# tractor_2v2.net
KiCad netlist of a schematic drawn in EAGLE
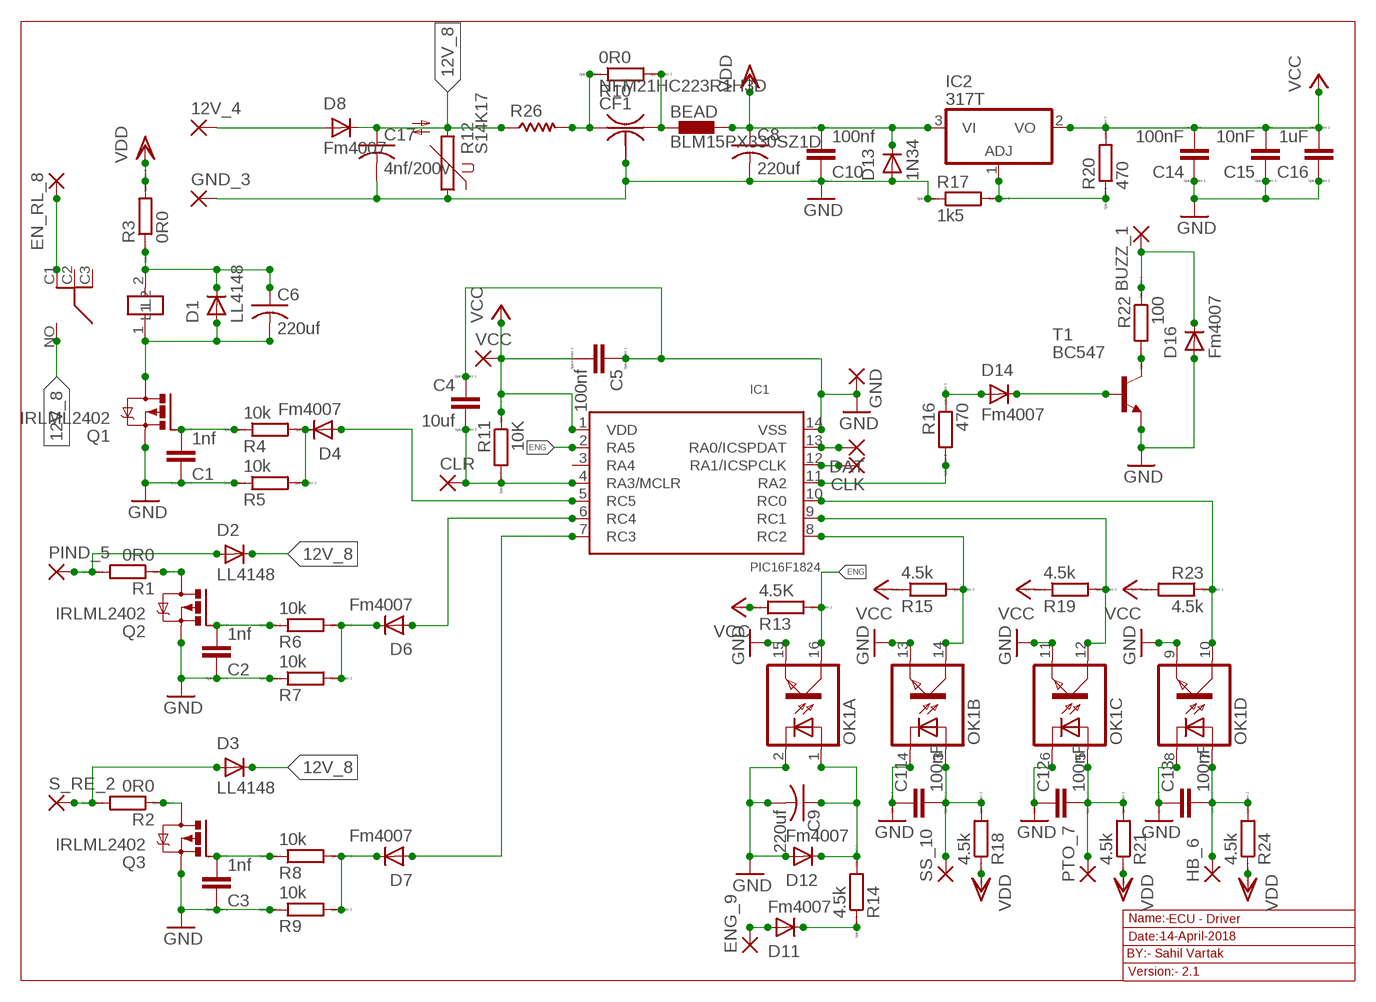
[diagram p0: schematic, sheet 1]

(export (version "E")
  (design (tool "Eeschema 10.0.6"))
  (components
    (comp (ref "12V_4")
      (value "2,54/1,1")
      (footprint "eagle-import:2,54_1,1")
      (libsource (lib "eagle-import") (part "2,54/1,1"))
    )
    (comp (ref "BEAD")
      (value "BLM15PX330SZ1D")
      (footprint "eagle-import:0402")
      (libsource (lib "eagle-import") (part "BLM15HG601SN1"))
    )
    (comp (ref "BUZZ_1")
      (value "2,54/1,1")
      (footprint "eagle-import:2,54_1,1")
      (libsource (lib "eagle-import") (part "2,54/1,1"))
    )
    (comp (ref "C1")
      (value "1nf")
      (footprint "eagle-import:C0603")
      (libsource (lib "eagle-import") (part "CC0603"))
    )
    (comp (ref "C2")
      (value "1nf")
      (footprint "eagle-import:C0603")
      (libsource (lib "eagle-import") (part "CC0603"))
    )
    (comp (ref "C3")
      (value "1nf")
      (footprint "eagle-import:C0603")
      (libsource (lib "eagle-import") (part "CC0603"))
    )
    (comp (ref "C4")
      (value "10uf")
      (footprint "eagle-import:C0603")
      (libsource (lib "eagle-import") (part "CC0603"))
    )
    (comp (ref "C5")
      (value "100nf")
      (footprint "eagle-import:C0603")
      (libsource (lib "eagle-import") (part "CC0603"))
    )
    (comp (ref "C6")
      (value "220uf")
      (footprint "eagle-import:C025-025X050")
      (libsource (lib "eagle-import") (part "C-US025-025X050"))
    )
    (comp (ref "C8")
      (value "220uf")
      (footprint "eagle-import:C025-025X050")
      (libsource (lib "eagle-import") (part "C-US025-025X050"))
    )
    (comp (ref "C9")
      (value "220uf")
      (footprint "eagle-import:C025-025X050")
      (libsource (lib "eagle-import") (part "C-US025-025X050"))
    )
    (comp (ref "C10")
      (value "100nf")
      (footprint "eagle-import:C0603")
      (libsource (lib "eagle-import") (part "CC0603"))
    )
    (comp (ref "C11")
      (value "100nF")
      (footprint "eagle-import:C0603")
      (libsource (lib "eagle-import") (part "CC0603"))
    )
    (comp (ref "C12")
      (value "100nF")
      (footprint "eagle-import:C0603")
      (libsource (lib "eagle-import") (part "CC0603"))
    )
    (comp (ref "C13")
      (value "100nF")
      (footprint "eagle-import:C0603")
      (libsource (lib "eagle-import") (part "CC0603"))
    )
    (comp (ref "C14")
      (value "100nF")
      (footprint "eagle-import:C0603")
      (libsource (lib "eagle-import") (part "CC0603"))
    )
    (comp (ref "C15")
      (value "10nF")
      (footprint "eagle-import:C0603")
      (libsource (lib "eagle-import") (part "CC0603"))
    )
    (comp (ref "C16")
      (value "1uF")
      (footprint "eagle-import:C0603")
      (libsource (lib "eagle-import") (part "CC0603"))
    )
    (comp (ref "C17")
      (value "4nf/200v")
      (footprint "eagle-import:C050-045X075")
      (libsource (lib "eagle-import") (part "C-US050-045X075"))
    )
    (comp (ref "CF1")
      (value "NFM21HC223R1H3D")
      (footprint "eagle-import:NFM3DC")
      (fields (field (name "MF") "FARNELL") (field (name "MPN") "NFM3DCC470U1H3L"))
      (libsource (lib "eagle-import") (part "NFM3DC"))
    )
    (comp (ref "CLK")
      (value "1,6/0,8")
      (footprint "eagle-import:1,6_0,8")
      (libsource (lib "eagle-import") (part "1,6/0,8"))
    )
    (comp (ref "CLR")
      (value "1,6/0,8")
      (footprint "eagle-import:1,6_0,8")
      (libsource (lib "eagle-import") (part "1,6/0,8"))
    )
    (comp (ref "D1")
      (value "LL4148")
      (footprint "eagle-import:SMA-DO214AC")
      (libsource (lib "eagle-import") (part "GF1"))
    )
    (comp (ref "D2")
      (value "LL4148")
      (footprint "eagle-import:SMA-DO214AC")
      (libsource (lib "eagle-import") (part "GF1"))
    )
    (comp (ref "D3")
      (value "LL4148")
      (footprint "eagle-import:SMA-DO214AC")
      (libsource (lib "eagle-import") (part "GF1"))
    )
    (comp (ref "D4")
      (value "Fm4007")
      (footprint "eagle-import:SMA-DO214AC")
      (libsource (lib "eagle-import") (part "GF1"))
    )
    (comp (ref "D6")
      (value "Fm4007")
      (footprint "eagle-import:SMA-DO214AC")
      (libsource (lib "eagle-import") (part "GF1"))
    )
    (comp (ref "D7")
      (value "Fm4007")
      (footprint "eagle-import:SMA-DO214AC")
      (libsource (lib "eagle-import") (part "GF1"))
    )
    (comp (ref "D8")
      (value "Fm4007")
      (footprint "eagle-import:SMA-DO214AC")
      (libsource (lib "eagle-import") (part "GF1"))
    )
    (comp (ref "D11")
      (value "Fm4007")
      (footprint "eagle-import:SMA-DO214AC")
      (libsource (lib "eagle-import") (part "GF1"))
    )
    (comp (ref "D12")
      (value "Fm4007")
      (footprint "eagle-import:SMA-DO214AC")
      (libsource (lib "eagle-import") (part "GF1"))
    )
    (comp (ref "D13")
      (value "1N34")
      (footprint "eagle-import:SMA-DO214AC")
      (libsource (lib "eagle-import") (part "GF1"))
    )
    (comp (ref "D14")
      (value "Fm4007")
      (footprint "eagle-import:SMA-DO214AC")
      (libsource (lib "eagle-import") (part "GF1"))
    )
    (comp (ref "D16")
      (value "Fm4007")
      (footprint "eagle-import:SMA-DO214AC")
      (libsource (lib "eagle-import") (part "GF1"))
    )
    (comp (ref "DAT")
      (value "1,6/0,8")
      (footprint "eagle-import:1,6_0,8")
      (libsource (lib "eagle-import") (part "1,6/0,8"))
    )
    (comp (ref "ENG_9")
      (value "2,54/1,1")
      (footprint "eagle-import:2,54_1,1")
      (libsource (lib "eagle-import") (part "2,54/1,1"))
    )
    (comp (ref "EN_RL_8")
      (value "2,54/1,1")
      (footprint "eagle-import:2,54_1,1")
      (libsource (lib "eagle-import") (part "2,54/1,1"))
    )
    (comp (ref "GND")
      (value "1,6/0,8")
      (footprint "eagle-import:1,6_0,8")
      (libsource (lib "eagle-import") (part "1,6/0,8"))
    )
    (comp (ref "GND_3")
      (value "2,54/1,1")
      (footprint "eagle-import:2,54_1,1")
      (libsource (lib "eagle-import") (part "2,54/1,1"))
    )
    (comp (ref "HB_6")
      (value "2,54/1,1")
      (footprint "eagle-import:2,54_1,1")
      (libsource (lib "eagle-import") (part "2,54/1,1"))
    )
    (comp (ref "IC1")
      (value "PIC16F1824")
      (footprint "eagle-import:SO-14")
      (libsource (lib "eagle-import") (part "PIC16F1824"))
    )
    (comp (ref "IC2")
      (value "317T")
      (footprint "eagle-import:TO220H")
      (libsource (lib "eagle-import") (part "317T"))
    )
    (comp (ref "K1")
      (value "RL703")
      (footprint "eagle-import:RL703")
      (libsource (lib "eagle-import") (part "RL703"))
    )
    (comp (ref "OK1")
      (value "TLP283-4")
      (footprint "eagle-import:MINI-FLAT-16")
      (libsource (lib "eagle-import") (part "TLP283-4"))
    )
    (comp (ref "PIND_5")
      (value "2,54/1,1")
      (footprint "eagle-import:2,54_1,1")
      (libsource (lib "eagle-import") (part "2,54/1,1"))
    )
    (comp (ref "PTO_7")
      (value "2,54/1,1")
      (footprint "eagle-import:2,54_1,1")
      (libsource (lib "eagle-import") (part "2,54/1,1"))
    )
    (comp (ref "Q1")
      (value "IRLML2402")
      (footprint "eagle-import:MICRO3")
      (libsource (lib "eagle-import") (part "IRLML5203"))
    )
    (comp (ref "Q2")
      (value "IRLML2402")
      (footprint "eagle-import:MICRO3")
      (libsource (lib "eagle-import") (part "IRLML5203"))
    )
    (comp (ref "Q3")
      (value "IRLML2402")
      (footprint "eagle-import:MICRO3")
      (libsource (lib "eagle-import") (part "IRLML5203"))
    )
    (comp (ref "R1")
      (value "0R0")
      (footprint "eagle-import:R0603")
      (libsource (lib "eagle-import") (part "RR0603"))
    )
    (comp (ref "R2")
      (value "0R0")
      (footprint "eagle-import:R0603")
      (libsource (lib "eagle-import") (part "RR0603"))
    )
    (comp (ref "R3")
      (value "0R0")
      (footprint "eagle-import:R0603")
      (libsource (lib "eagle-import") (part "RR0603"))
    )
    (comp (ref "R4")
      (value "10k")
      (footprint "eagle-import:R0603")
      (libsource (lib "eagle-import") (part "RR0603"))
    )
    (comp (ref "R5")
      (value "10k")
      (footprint "eagle-import:R0603")
      (libsource (lib "eagle-import") (part "RR0603"))
    )
    (comp (ref "R6")
      (value "10k")
      (footprint "eagle-import:R0603")
      (libsource (lib "eagle-import") (part "RR0603"))
    )
    (comp (ref "R7")
      (value "10k")
      (footprint "eagle-import:R0603")
      (libsource (lib "eagle-import") (part "RR0603"))
    )
    (comp (ref "R8")
      (value "10k")
      (footprint "eagle-import:R0603")
      (libsource (lib "eagle-import") (part "RR0603"))
    )
    (comp (ref "R9")
      (value "10k")
      (footprint "eagle-import:R0603")
      (libsource (lib "eagle-import") (part "RR0603"))
    )
    (comp (ref "R10")
      (value "0R0")
      (footprint "eagle-import:R0603")
      (libsource (lib "eagle-import") (part "RR0603"))
    )
    (comp (ref "R11")
      (value "10K")
      (footprint "eagle-import:R0603")
      (libsource (lib "eagle-import") (part "RR0603"))
    )
    (comp (ref "R12")
      (value "S14K17")
      (footprint "eagle-import:S14K17")
      (libsource (lib "eagle-import") (part "S14K17"))
    )
    (comp (ref "R13")
      (value "4.5K")
      (footprint "eagle-import:R0603")
      (libsource (lib "eagle-import") (part "RR0603"))
    )
    (comp (ref "R14")
      (value "4.5k")
      (footprint "eagle-import:R0603")
      (libsource (lib "eagle-import") (part "RR0603"))
    )
    (comp (ref "R15")
      (value "4.5k")
      (footprint "eagle-import:R0603")
      (libsource (lib "eagle-import") (part "RR0603"))
    )
    (comp (ref "R16")
      (value "470")
      (footprint "eagle-import:R0603")
      (libsource (lib "eagle-import") (part "RR0603"))
    )
    (comp (ref "R17")
      (value "1k5")
      (footprint "eagle-import:R0603")
      (libsource (lib "eagle-import") (part "RR0603"))
    )
    (comp (ref "R18")
      (value "4.5k")
      (footprint "eagle-import:R0603")
      (libsource (lib "eagle-import") (part "RR0603"))
    )
    (comp (ref "R19")
      (value "4.5k")
      (footprint "eagle-import:R0603")
      (libsource (lib "eagle-import") (part "RR0603"))
    )
    (comp (ref "R20")
      (value "470")
      (footprint "eagle-import:R0603")
      (libsource (lib "eagle-import") (part "RR0603"))
    )
    (comp (ref "R21")
      (value "4.5k")
      (footprint "eagle-import:R0603")
      (libsource (lib "eagle-import") (part "RR0603"))
    )
    (comp (ref "R22")
      (value "100")
      (footprint "eagle-import:R0603")
      (libsource (lib "eagle-import") (part "RR0603"))
    )
    (comp (ref "R23")
      (value "4.5k")
      (footprint "eagle-import:R0603")
      (libsource (lib "eagle-import") (part "RR0603"))
    )
    (comp (ref "R24")
      (value "4.5k")
      (footprint "eagle-import:R0603")
      (libsource (lib "eagle-import") (part "RR0603"))
    )
    (comp (ref "R26")
      (value "R-US_WSC2515")
      (footprint "eagle-import:WSC2515")
      (libsource (lib "eagle-import") (part "R-US_WSC2515"))
    )
    (comp (ref "SS_10")
      (value "2,54/1,1")
      (footprint "eagle-import:2,54_1,1")
      (libsource (lib "eagle-import") (part "2,54/1,1"))
    )
    (comp (ref "S_RE_2")
      (value "2,54/1,1")
      (footprint "eagle-import:2,54_1,1")
      (libsource (lib "eagle-import") (part "2,54/1,1"))
    )
    (comp (ref "T1")
      (value "BC547")
      (footprint "eagle-import:TO92")
      (libsource (lib "eagle-import") (part "BC547"))
    )
    (comp (ref "VCC")
      (value "1,6/0,8")
      (footprint "eagle-import:1,6_0,8")
      (libsource (lib "eagle-import") (part "1,6/0,8"))
    )
  )
  (nets
    (net (code "1") (name "12V_8") (class "Default")
      (node (ref "C17") (pin "1") (pinfunction "1_1") (pintype "passive"))
      (node (ref "D2") (pin "K") (pinfunction "C_K") (pintype "passive"))
      (node (ref "D3") (pin "K") (pinfunction "C_K") (pintype "passive"))
      (node (ref "D8") (pin "K") (pinfunction "C_K") (pintype "passive"))
      (node (ref "K1") (pin "NO") (pinfunction "NO_NO") (pintype "bidirectional"))
      (node (ref "R12") (pin "2") (pinfunction "2_2") (pintype "passive"))
      (node (ref "R26") (pin "1") (pinfunction "1_1") (pintype "passive"))
    )
    (net (code "2") (name "ENG") (class "Default")
      (node (ref "IC1") (pin "2") (pinfunction "RA5_2") (pintype "bidirectional"))
      (node (ref "OK1") (pin "16") (pinfunction "COL_16") (pintype "passive"))
      (node (ref "R13") (pin "2") (pinfunction "2_2") (pintype "passive"))
    )
    (net (code "3") (name "GND") (class "Default")
      (node (ref "C1") (pin "1") (pinfunction "1_1") (pintype "passive"))
      (node (ref "C10") (pin "1") (pinfunction "1_1") (pintype "passive"))
      (node (ref "C11") (pin "1") (pinfunction "1_1") (pintype "passive"))
      (node (ref "C12") (pin "1") (pinfunction "1_1") (pintype "passive"))
      (node (ref "C13") (pin "1") (pinfunction "1_1") (pintype "passive"))
      (node (ref "C14") (pin "1") (pinfunction "1_1") (pintype "passive"))
      (node (ref "C15") (pin "1") (pinfunction "1_1") (pintype "passive"))
      (node (ref "C16") (pin "1") (pinfunction "1_1") (pintype "passive"))
      (node (ref "C17") (pin "2") (pinfunction "2_2") (pintype "passive"))
      (node (ref "C2") (pin "1") (pinfunction "1_1") (pintype "passive"))
      (node (ref "C3") (pin "1") (pinfunction "1_1") (pintype "passive"))
      (node (ref "C4") (pin "1") (pinfunction "1_1") (pintype "passive"))
      (node (ref "C5") (pin "1") (pinfunction "1_1") (pintype "passive"))
      (node (ref "C8") (pin "2") (pinfunction "2_2") (pintype "passive"))
      (node (ref "C9") (pin "2") (pinfunction "2_2") (pintype "passive"))
      (node (ref "CF1") (pin "2@1") (pinfunction "2_2@1") (pintype "passive"))
      (node (ref "D12") (pin "A") (pinfunction "A_A") (pintype "passive"))
      (node (ref "D13") (pin "A") (pinfunction "A_A") (pintype "passive"))
      (node (ref "D16") (pin "A") (pinfunction "A_A") (pintype "passive"))
      (node (ref "GND") (pin "1") (pinfunction "P_1") (pintype "passive"))
      (node (ref "GND_3") (pin "1") (pinfunction "P_1") (pintype "passive"))
      (node (ref "IC1") (pin "14") (pinfunction "VSS_14") (pintype "bidirectional"))
      (node (ref "OK1") (pin "11") (pinfunction "EMIT_11") (pintype "passive"))
      (node (ref "OK1") (pin "13") (pinfunction "EMIT_13") (pintype "passive"))
      (node (ref "OK1") (pin "15") (pinfunction "EMIT_15") (pintype "passive"))
      (node (ref "OK1") (pin "2") (pinfunction "C_2") (pintype "passive"))
      (node (ref "OK1") (pin "4") (pinfunction "C_4") (pintype "passive"))
      (node (ref "OK1") (pin "6") (pinfunction "C_6") (pintype "passive"))
      (node (ref "OK1") (pin "8") (pinfunction "C_8") (pintype "passive"))
      (node (ref "OK1") (pin "9") (pinfunction "EMIT_9") (pintype "passive"))
      (node (ref "Q1") (pin "2") (pinfunction "S_2") (pintype "passive"))
      (node (ref "Q2") (pin "2") (pinfunction "S_2") (pintype "passive"))
      (node (ref "Q3") (pin "2") (pinfunction "S_2") (pintype "passive"))
      (node (ref "R12") (pin "1") (pinfunction "1_1") (pintype "passive"))
      (node (ref "R17") (pin "1") (pinfunction "1_1") (pintype "passive"))
      (node (ref "R5") (pin "1") (pinfunction "1_1") (pintype "passive"))
      (node (ref "R7") (pin "1") (pinfunction "1_1") (pintype "passive"))
      (node (ref "R9") (pin "1") (pinfunction "1_1") (pintype "passive"))
      (node (ref "T1") (pin "1") (pinfunction "E_1") (pintype "passive"))
    )
    (net (code "4") (name "Net-(12V_4-P)") (class "Default")
      (node (ref "12V_4") (pin "1") (pinfunction "P_1") (pintype "passive"))
      (node (ref "D8") (pin "A") (pinfunction "A_A") (pintype "passive"))
    )
    (net (code "5") (name "Net-(BEAD-Pad1)") (class "Default")
      (node (ref "BEAD") (pin "1") (pinfunction "1_1") (pintype "passive"))
      (node (ref "CF1") (pin "3") (pinfunction "3_3") (pintype "passive"))
      (node (ref "R10") (pin "2") (pinfunction "2_2") (pintype "passive"))
    )
    (net (code "6") (name "Net-(BUZZ_1-P)") (class "Default")
      (node (ref "BUZZ_1") (pin "1") (pinfunction "P_1") (pintype "passive"))
      (node (ref "D16") (pin "K") (pinfunction "C_K") (pintype "passive"))
      (node (ref "R22") (pin "1") (pinfunction "1_1") (pintype "passive"))
    )
    (net (code "7") (name "Net-(CF1-Pad1)") (class "Default")
      (node (ref "CF1") (pin "1") (pinfunction "1_1") (pintype "passive"))
      (node (ref "R10") (pin "1") (pinfunction "1_1") (pintype "passive"))
      (node (ref "R26") (pin "2") (pinfunction "2_2") (pintype "passive"))
    )
    (net (code "8") (name "Net-(CLK-P)") (class "Default")
      (node (ref "CLK") (pin "1") (pinfunction "P_1") (pintype "passive"))
      (node (ref "IC1") (pin "12") (pinfunction "RA1/ICSPCLK_12") (pintype "bidirectional"))
    )
    (net (code "9") (name "Net-(CLR-P)") (class "Default")
      (node (ref "C4") (pin "2") (pinfunction "2_2") (pintype "passive"))
      (node (ref "CLR") (pin "1") (pinfunction "P_1") (pintype "passive"))
      (node (ref "IC1") (pin "4") (pinfunction "RA3/MCLR_4") (pintype "bidirectional"))
      (node (ref "R11") (pin "2") (pinfunction "2_2") (pintype "passive"))
    )
    (net (code "10") (name "Net-(D1-C)") (class "Default")
      (node (ref "C6") (pin "1") (pinfunction "1_1") (pintype "passive"))
      (node (ref "D1") (pin "K") (pinfunction "C_K") (pintype "passive"))
      (node (ref "K1") (pin "2") (pinfunction "L1_2") (pintype "bidirectional"))
      (node (ref "R3") (pin "1") (pinfunction "1_1") (pintype "passive"))
    )
    (net (code "11") (name "Net-(D4-C)") (class "Default")
      (node (ref "D4") (pin "K") (pinfunction "C_K") (pintype "passive"))
      (node (ref "R4") (pin "2") (pinfunction "2_2") (pintype "passive"))
      (node (ref "R5") (pin "2") (pinfunction "2_2") (pintype "passive"))
    )
    (net (code "12") (name "Net-(D6-C)") (class "Default")
      (node (ref "D6") (pin "K") (pinfunction "C_K") (pintype "passive"))
      (node (ref "R6") (pin "2") (pinfunction "2_2") (pintype "passive"))
      (node (ref "R7") (pin "2") (pinfunction "2_2") (pintype "passive"))
    )
    (net (code "13") (name "Net-(D7-C)") (class "Default")
      (node (ref "D7") (pin "K") (pinfunction "C_K") (pintype "passive"))
      (node (ref "R8") (pin "2") (pinfunction "2_2") (pintype "passive"))
      (node (ref "R9") (pin "2") (pinfunction "2_2") (pintype "passive"))
    )
    (net (code "14") (name "Net-(D11-C)") (class "Default")
      (node (ref "D11") (pin "K") (pinfunction "C_K") (pintype "passive"))
      (node (ref "R14") (pin "1") (pinfunction "1_1") (pintype "passive"))
    )
    (net (code "15") (name "Net-(D12-C)") (class "Default")
      (node (ref "C9") (pin "1") (pinfunction "1_1") (pintype "passive"))
      (node (ref "D12") (pin "K") (pinfunction "C_K") (pintype "passive"))
      (node (ref "OK1") (pin "1") (pinfunction "A_1") (pintype "passive"))
      (node (ref "R14") (pin "2") (pinfunction "2_2") (pintype "passive"))
    )
    (net (code "16") (name "Net-(D14-C)") (class "Default")
      (node (ref "D14") (pin "K") (pinfunction "C_K") (pintype "passive"))
      (node (ref "T1") (pin "2") (pinfunction "B_2") (pintype "passive"))
    )
    (net (code "17") (name "Net-(D14-PadA)") (class "Default")
      (node (ref "D14") (pin "A") (pinfunction "A_A") (pintype "passive"))
      (node (ref "R16") (pin "1") (pinfunction "1_1") (pintype "passive"))
    )
    (net (code "18") (name "Net-(DAT-P)") (class "Default")
      (node (ref "DAT") (pin "1") (pinfunction "P_1") (pintype "passive"))
      (node (ref "IC1") (pin "13") (pinfunction "RA0/ICSPDAT_13") (pintype "bidirectional"))
    )
    (net (code "19") (name "Net-(ENG_9-P)") (class "Default")
      (node (ref "D11") (pin "A") (pinfunction "A_A") (pintype "passive"))
      (node (ref "ENG_9") (pin "1") (pinfunction "P_1") (pintype "passive"))
    )
    (net (code "20") (name "Net-(EN_RL_8-P)") (class "Default")
      (node (ref "EN_RL_8") (pin "1") (pinfunction "P_1") (pintype "passive"))
      (node (ref "K1") (pin "C1") (pinfunction "C1_C1") (pintype "bidirectional"))
    )
    (net (code "21") (name "Net-(HB_6-P)") (class "Default")
      (node (ref "C13") (pin "2") (pinfunction "2_2") (pintype "passive"))
      (node (ref "HB_6") (pin "1") (pinfunction "P_1") (pintype "passive"))
      (node (ref "OK1") (pin "7") (pinfunction "A_7") (pintype "passive"))
      (node (ref "R24") (pin "2") (pinfunction "2_2") (pintype "passive"))
    )
    (net (code "22") (name "Net-(IC1-RA2)") (class "Default")
      (node (ref "IC1") (pin "11") (pinfunction "RA2_11") (pintype "bidirectional"))
      (node (ref "R16") (pin "2") (pinfunction "2_2") (pintype "passive"))
    )
    (net (code "23") (name "Net-(IC1-RC0)") (class "Default")
      (node (ref "IC1") (pin "10") (pinfunction "RC0_10") (pintype "bidirectional"))
      (node (ref "OK1") (pin "10") (pinfunction "COL_10") (pintype "passive"))
      (node (ref "R23") (pin "1") (pinfunction "1_1") (pintype "passive"))
    )
    (net (code "24") (name "Net-(IC1-RC1)") (class "Default")
      (node (ref "IC1") (pin "9") (pinfunction "RC1_9") (pintype "bidirectional"))
      (node (ref "OK1") (pin "12") (pinfunction "COL_12") (pintype "passive"))
      (node (ref "R19") (pin "2") (pinfunction "2_2") (pintype "passive"))
    )
    (net (code "25") (name "Net-(IC1-RC2)") (class "Default")
      (node (ref "IC1") (pin "8") (pinfunction "RC2_8") (pintype "bidirectional"))
      (node (ref "OK1") (pin "14") (pinfunction "COL_14") (pintype "passive"))
      (node (ref "R15") (pin "2") (pinfunction "2_2") (pintype "passive"))
    )
    (net (code "26") (name "Net-(IC1-RC3)") (class "Default")
      (node (ref "D7") (pin "A") (pinfunction "A_A") (pintype "passive"))
      (node (ref "IC1") (pin "7") (pinfunction "RC3_7") (pintype "bidirectional"))
    )
    (net (code "27") (name "Net-(IC1-RC4)") (class "Default")
      (node (ref "D6") (pin "A") (pinfunction "A_A") (pintype "passive"))
      (node (ref "IC1") (pin "6") (pinfunction "RC4_6") (pintype "bidirectional"))
    )
    (net (code "28") (name "Net-(IC1-RC5)") (class "Default")
      (node (ref "D4") (pin "A") (pinfunction "A_A") (pintype "passive"))
      (node (ref "IC1") (pin "5") (pinfunction "RC5_5") (pintype "bidirectional"))
    )
    (net (code "29") (name "Net-(IC2-ADJ)") (class "Default")
      (node (ref "IC2") (pin "1") (pinfunction "ADJ_1") (pintype "input"))
      (node (ref "R17") (pin "2") (pinfunction "2_2") (pintype "passive"))
      (node (ref "R20") (pin "1") (pinfunction "1_1") (pintype "passive"))
    )
    (net (code "30") (name "Net-(K1-L2)") (class "Default")
      (node (ref "C6") (pin "2") (pinfunction "2_2") (pintype "passive"))
      (node (ref "D1") (pin "A") (pinfunction "A_A") (pintype "passive"))
      (node (ref "K1") (pin "1") (pinfunction "L2_1") (pintype "bidirectional"))
      (node (ref "Q1") (pin "3") (pinfunction "D_3") (pintype "passive"))
    )
    (net (code "31") (name "Net-(OK1B-A)") (class "Default")
      (node (ref "C11") (pin "2") (pinfunction "2_2") (pintype "passive"))
      (node (ref "OK1") (pin "3") (pinfunction "A_3") (pintype "passive"))
      (node (ref "R18") (pin "2") (pinfunction "2_2") (pintype "passive"))
      (node (ref "SS_10") (pin "1") (pinfunction "P_1") (pintype "passive"))
    )
    (net (code "32") (name "Net-(OK1C-A)") (class "Default")
      (node (ref "C12") (pin "2") (pinfunction "2_2") (pintype "passive"))
      (node (ref "OK1") (pin "5") (pinfunction "A_5") (pintype "passive"))
      (node (ref "PTO_7") (pin "1") (pinfunction "P_1") (pintype "passive"))
      (node (ref "R21") (pin "2") (pinfunction "2_2") (pintype "passive"))
    )
    (net (code "33") (name "Net-(PIND_5-P)") (class "Default")
      (node (ref "D2") (pin "A") (pinfunction "A_A") (pintype "passive"))
      (node (ref "PIND_5") (pin "1") (pinfunction "P_1") (pintype "passive"))
      (node (ref "R1") (pin "2") (pinfunction "2_2") (pintype "passive"))
    )
    (net (code "34") (name "Net-(Q1-G)") (class "Default")
      (node (ref "C1") (pin "2") (pinfunction "2_2") (pintype "passive"))
      (node (ref "Q1") (pin "1") (pinfunction "G_1") (pintype "passive"))
      (node (ref "R4") (pin "1") (pinfunction "1_1") (pintype "passive"))
    )
    (net (code "35") (name "Net-(Q2-D)") (class "Default")
      (node (ref "Q2") (pin "3") (pinfunction "D_3") (pintype "passive"))
      (node (ref "R1") (pin "1") (pinfunction "1_1") (pintype "passive"))
    )
    (net (code "36") (name "Net-(Q2-G)") (class "Default")
      (node (ref "C2") (pin "2") (pinfunction "2_2") (pintype "passive"))
      (node (ref "Q2") (pin "1") (pinfunction "G_1") (pintype "passive"))
      (node (ref "R6") (pin "1") (pinfunction "1_1") (pintype "passive"))
    )
    (net (code "37") (name "Net-(Q3-D)") (class "Default")
      (node (ref "Q3") (pin "3") (pinfunction "D_3") (pintype "passive"))
      (node (ref "R2") (pin "1") (pinfunction "1_1") (pintype "passive"))
    )
    (net (code "38") (name "Net-(Q3-G)") (class "Default")
      (node (ref "C3") (pin "2") (pinfunction "2_2") (pintype "passive"))
      (node (ref "Q3") (pin "1") (pinfunction "G_1") (pintype "passive"))
      (node (ref "R8") (pin "1") (pinfunction "1_1") (pintype "passive"))
    )
    (net (code "39") (name "Net-(S_RE_2-P)") (class "Default")
      (node (ref "D3") (pin "A") (pinfunction "A_A") (pintype "passive"))
      (node (ref "R2") (pin "2") (pinfunction "2_2") (pintype "passive"))
      (node (ref "S_RE_2") (pin "1") (pinfunction "P_1") (pintype "passive"))
    )
    (net (code "40") (name "Net-(T1-C)") (class "Default")
      (node (ref "R22") (pin "2") (pinfunction "2_2") (pintype "passive"))
      (node (ref "T1") (pin "3") (pinfunction "C_3") (pintype "passive"))
    )
    (net (code "41") (name "VCC") (class "Default")
      (node (ref "C14") (pin "2") (pinfunction "2_2") (pintype "passive"))
      (node (ref "C15") (pin "2") (pinfunction "2_2") (pintype "passive"))
      (node (ref "C16") (pin "2") (pinfunction "2_2") (pintype "passive"))
      (node (ref "C5") (pin "2") (pinfunction "2_2") (pintype "passive"))
      (node (ref "IC1") (pin "1") (pinfunction "VDD_1") (pintype "bidirectional"))
      (node (ref "IC2") (pin "2") (pinfunction "VO_2") (pintype "passive"))
      (node (ref "R11") (pin "1") (pinfunction "1_1") (pintype "passive"))
      (node (ref "R13") (pin "1") (pinfunction "1_1") (pintype "passive"))
      (node (ref "R15") (pin "1") (pinfunction "1_1") (pintype "passive"))
      (node (ref "R19") (pin "1") (pinfunction "1_1") (pintype "passive"))
      (node (ref "R20") (pin "2") (pinfunction "2_2") (pintype "passive"))
      (node (ref "R23") (pin "2") (pinfunction "2_2") (pintype "passive"))
      (node (ref "VCC") (pin "1") (pinfunction "P_1") (pintype "passive"))
    )
    (net (code "42") (name "VDD") (class "Default")
      (node (ref "BEAD") (pin "2") (pinfunction "2_2") (pintype "passive"))
      (node (ref "C10") (pin "2") (pinfunction "2_2") (pintype "passive"))
      (node (ref "C8") (pin "1") (pinfunction "1_1") (pintype "passive"))
      (node (ref "D13") (pin "K") (pinfunction "C_K") (pintype "passive"))
      (node (ref "IC2") (pin "3") (pinfunction "VI_3") (pintype "input"))
      (node (ref "R18") (pin "1") (pinfunction "1_1") (pintype "passive"))
      (node (ref "R21") (pin "1") (pinfunction "1_1") (pintype "passive"))
      (node (ref "R24") (pin "1") (pinfunction "1_1") (pintype "passive"))
      (node (ref "R3") (pin "2") (pinfunction "2_2") (pintype "passive"))
    )
    (net (code "43") (name "unconnected-(CF1-2-Pad2@2)") (class "Default")
      (node (ref "CF1") (pin "2@2") (pinfunction "2_2@2") (pintype "passive"))
    )
    (net (code "44") (name "unconnected-(IC1-RA4-Pad3)") (class "Default")
      (node (ref "IC1") (pin "3") (pinfunction "RA4_3") (pintype "bidirectional"))
    )
    (net (code "45") (name "unconnected-(K1-PadC2)") (class "Default")
      (node (ref "K1") (pin "C2") (pinfunction "C2_C2") (pintype "bidirectional"))
    )
    (net (code "46") (name "unconnected-(K1-PadC3)") (class "Default")
      (node (ref "K1") (pin "C3") (pinfunction "C3_C3") (pintype "bidirectional"))
    )
  )
)
